# mega_shield_0_1.net
KiCad netlist of a schematic drawn in EAGLE
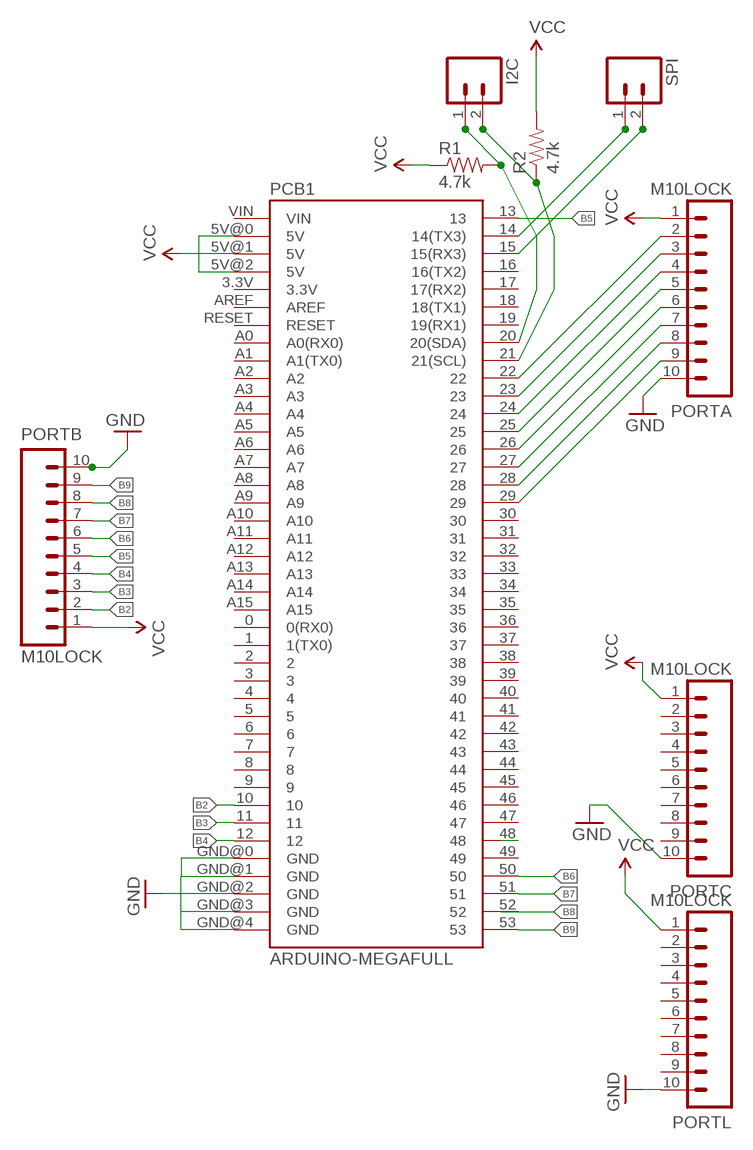
[diagram p0: schematic, sheet 1]

(export (version "E")
  (design (tool "Eeschema 10.0.6"))
  (components
    (comp (ref "I2C")
      (value "M02PTH")
      (footprint "eagle-import:1X02")
      (libsource (lib "eagle-import") (part "M02PTH"))
    )
    (comp (ref "PCB1")
      (value "ARDUINO-MEGAFULL")
      (footprint "eagle-import:ARDUINO_MEGA")
      (libsource (lib "eagle-import") (part "ARDUINO-MEGAFULL"))
    )
    (comp (ref "PORTA")
      (value "M10LOCK")
      (footprint "eagle-import:1X10_LOCK")
      (libsource (lib "eagle-import") (part "M10LOCK"))
    )
    (comp (ref "PORTB")
      (value "M10LOCK")
      (footprint "eagle-import:1X10_LOCK")
      (libsource (lib "eagle-import") (part "M10LOCK"))
    )
    (comp (ref "PORTC")
      (value "M10LOCK")
      (footprint "eagle-import:1X10_LOCK")
      (libsource (lib "eagle-import") (part "M10LOCK"))
    )
    (comp (ref "PORTL")
      (value "M10LOCK")
      (footprint "eagle-import:1X10_LOCK")
      (libsource (lib "eagle-import") (part "M10LOCK"))
    )
    (comp (ref "R1")
      (value "4.7k")
      (footprint "eagle-import:AXIAL-0.3")
      (libsource (lib "eagle-import") (part "RESISTORPTH1"))
    )
    (comp (ref "R2")
      (value "4.7k")
      (footprint "eagle-import:AXIAL-0.3")
      (libsource (lib "eagle-import") (part "RESISTORPTH1"))
    )
    (comp (ref "SPI")
      (value "M02PTH")
      (footprint "eagle-import:1X02")
      (libsource (lib "eagle-import") (part "M02PTH"))
    )
  )
  (nets
    (net (code "1") (name "B2") (class "Default")
      (node (ref "PCB1") (pin "10") (pinfunction "10_10") (pintype "bidirectional"))
      (node (ref "PORTB") (pin "2") (pinfunction "2_2") (pintype "passive"))
    )
    (net (code "2") (name "B3") (class "Default")
      (node (ref "PCB1") (pin "11") (pinfunction "11_11") (pintype "bidirectional"))
      (node (ref "PORTB") (pin "3") (pinfunction "3_3") (pintype "passive"))
    )
    (net (code "3") (name "B4") (class "Default")
      (node (ref "PCB1") (pin "12") (pinfunction "12_12") (pintype "bidirectional"))
      (node (ref "PORTB") (pin "4") (pinfunction "4_4") (pintype "passive"))
    )
    (net (code "4") (name "B5") (class "Default")
      (node (ref "PCB1") (pin "13") (pinfunction "13_13") (pintype "bidirectional"))
      (node (ref "PORTB") (pin "5") (pinfunction "5_5") (pintype "passive"))
    )
    (net (code "5") (name "B6") (class "Default")
      (node (ref "PCB1") (pin "50") (pinfunction "50_50") (pintype "bidirectional"))
      (node (ref "PORTB") (pin "6") (pinfunction "6_6") (pintype "passive"))
    )
    (net (code "6") (name "B7") (class "Default")
      (node (ref "PCB1") (pin "51") (pinfunction "51_51") (pintype "bidirectional"))
      (node (ref "PORTB") (pin "7") (pinfunction "7_7") (pintype "passive"))
    )
    (net (code "7") (name "B8") (class "Default")
      (node (ref "PORTB") (pin "8") (pinfunction "8_8") (pintype "passive"))
    )
    (net (code "8") (name "B9") (class "Default")
      (node (ref "PCB1") (pin "53") (pinfunction "53_53") (pintype "bidirectional"))
      (node (ref "PORTB") (pin "9") (pinfunction "9_9") (pintype "passive"))
    )
    (net (code "9") (name "GND") (class "Default")
      (node (ref "PCB1") (pin "GND@0") (pinfunction "GND_GND@0") (pintype "bidirectional"))
      (node (ref "PCB1") (pin "GND@1") (pinfunction "GND_GND@1") (pintype "bidirectional"))
      (node (ref "PCB1") (pin "GND@2") (pinfunction "GND_GND@2") (pintype "bidirectional"))
      (node (ref "PCB1") (pin "GND@3") (pinfunction "GND_GND@3") (pintype "bidirectional"))
      (node (ref "PCB1") (pin "GND@4") (pinfunction "GND_GND@4") (pintype "bidirectional"))
      (node (ref "PORTA") (pin "10") (pinfunction "10_10") (pintype "passive"))
      (node (ref "PORTB") (pin "10") (pinfunction "10_10") (pintype "passive"))
      (node (ref "PORTC") (pin "10") (pinfunction "10_10") (pintype "passive"))
      (node (ref "PORTL") (pin "10") (pinfunction "10_10") (pintype "passive"))
    )
    (net (code "10") (name "Net-(PCB1-14(TX3))") (class "Default")
      (node (ref "PCB1") (pin "14") (pinfunction "14(TX3)_14") (pintype "bidirectional"))
      (node (ref "SPI") (pin "1") (pinfunction "1_1") (pintype "passive"))
    )
    (net (code "11") (name "Net-(PCB1-15(RX3))") (class "Default")
      (node (ref "PCB1") (pin "15") (pinfunction "15(RX3)_15") (pintype "bidirectional"))
      (node (ref "SPI") (pin "2") (pinfunction "2_2") (pintype "passive"))
    )
    (net (code "12") (name "Net-(PCB1-20(SDA))") (class "Default")
      (node (ref "I2C") (pin "1") (pinfunction "1_1") (pintype "passive"))
      (node (ref "PCB1") (pin "20") (pinfunction "20(SDA)_20") (pintype "bidirectional"))
      (node (ref "R1") (pin "P$2") (pinfunction "2_P$2") (pintype "passive"))
    )
    (net (code "13") (name "Net-(PCB1-21(SCL))") (class "Default")
      (node (ref "I2C") (pin "2") (pinfunction "2_2") (pintype "passive"))
      (node (ref "PCB1") (pin "21") (pinfunction "21(SCL)_21") (pintype "bidirectional"))
      (node (ref "R2") (pin "P$1") (pinfunction "1_P$1") (pintype "passive"))
    )
    (net (code "14") (name "Net-(PCB1-Pad22)") (class "Default")
      (node (ref "PCB1") (pin "22") (pinfunction "22_22") (pintype "bidirectional"))
      (node (ref "PORTA") (pin "2") (pinfunction "2_2") (pintype "passive"))
    )
    (net (code "15") (name "Net-(PCB1-Pad23)") (class "Default")
      (node (ref "PCB1") (pin "23") (pinfunction "23_23") (pintype "bidirectional"))
      (node (ref "PORTA") (pin "3") (pinfunction "3_3") (pintype "passive"))
    )
    (net (code "16") (name "Net-(PCB1-Pad24)") (class "Default")
      (node (ref "PCB1") (pin "24") (pinfunction "24_24") (pintype "bidirectional"))
      (node (ref "PORTA") (pin "4") (pinfunction "4_4") (pintype "passive"))
    )
    (net (code "17") (name "Net-(PCB1-Pad25)") (class "Default")
      (node (ref "PCB1") (pin "25") (pinfunction "25_25") (pintype "bidirectional"))
      (node (ref "PORTA") (pin "5") (pinfunction "5_5") (pintype "passive"))
    )
    (net (code "18") (name "Net-(PCB1-Pad26)") (class "Default")
      (node (ref "PCB1") (pin "26") (pinfunction "26_26") (pintype "bidirectional"))
      (node (ref "PORTA") (pin "6") (pinfunction "6_6") (pintype "passive"))
    )
    (net (code "19") (name "Net-(PCB1-Pad27)") (class "Default")
      (node (ref "PCB1") (pin "27") (pinfunction "27_27") (pintype "bidirectional"))
      (node (ref "PORTA") (pin "7") (pinfunction "7_7") (pintype "passive"))
    )
    (net (code "20") (name "Net-(PCB1-Pad28)") (class "Default")
      (node (ref "PCB1") (pin "28") (pinfunction "28_28") (pintype "bidirectional"))
      (node (ref "PORTA") (pin "8") (pinfunction "8_8") (pintype "passive"))
    )
    (net (code "21") (name "Net-(PCB1-Pad29)") (class "Default")
      (node (ref "PCB1") (pin "29") (pinfunction "29_29") (pintype "bidirectional"))
      (node (ref "PORTA") (pin "9") (pinfunction "9_9") (pintype "passive"))
    )
    (net (code "22") (name "VCC") (class "Default")
      (node (ref "PCB1") (pin "5V@0") (pinfunction "5V_5V@0") (pintype "bidirectional"))
      (node (ref "PCB1") (pin "5V@1") (pinfunction "5V_5V@1") (pintype "bidirectional"))
      (node (ref "PCB1") (pin "5V@2") (pinfunction "5V_5V@2") (pintype "bidirectional"))
      (node (ref "PORTA") (pin "1") (pinfunction "1_1") (pintype "passive"))
      (node (ref "PORTB") (pin "1") (pinfunction "1_1") (pintype "passive"))
      (node (ref "PORTC") (pin "1") (pinfunction "1_1") (pintype "passive"))
      (node (ref "PORTL") (pin "1") (pinfunction "1_1") (pintype "passive"))
      (node (ref "R1") (pin "P$1") (pinfunction "1_P$1") (pintype "passive"))
      (node (ref "R2") (pin "P$2") (pinfunction "2_P$2") (pintype "passive"))
    )
    (net (code "23") (name "unconnected-(PCB1-0(RX0)-Pad0)") (class "Default")
      (node (ref "PCB1") (pin "0") (pinfunction "0(RX0)_0") (pintype "bidirectional"))
    )
    (net (code "24") (name "unconnected-(PCB1-1(TX0)-Pad1)") (class "Default")
      (node (ref "PCB1") (pin "1") (pinfunction "1(TX0)_1") (pintype "bidirectional"))
    )
    (net (code "25") (name "unconnected-(PCB1-16(TX2)-Pad16)") (class "Default")
      (node (ref "PCB1") (pin "16") (pinfunction "16(TX2)_16") (pintype "bidirectional"))
    )
    (net (code "26") (name "unconnected-(PCB1-17(RX2)-Pad17)") (class "Default")
      (node (ref "PCB1") (pin "17") (pinfunction "17(RX2)_17") (pintype "bidirectional"))
    )
    (net (code "27") (name "unconnected-(PCB1-18(TX1)-Pad18)") (class "Default")
      (node (ref "PCB1") (pin "18") (pinfunction "18(TX1)_18") (pintype "bidirectional"))
    )
    (net (code "28") (name "unconnected-(PCB1-19(RX1)-Pad19)") (class "Default")
      (node (ref "PCB1") (pin "19") (pinfunction "19(RX1)_19") (pintype "bidirectional"))
    )
    (net (code "29") (name "unconnected-(PCB1-A0(RX0)-PadA0)") (class "Default")
      (node (ref "PCB1") (pin "A0") (pinfunction "A0(RX0)_A0") (pintype "bidirectional"))
    )
    (net (code "30") (name "unconnected-(PCB1-A1(TX0)-PadA1)") (class "Default")
      (node (ref "PCB1") (pin "A1") (pinfunction "A1(TX0)_A1") (pintype "bidirectional"))
    )
    (net (code "31") (name "unconnected-(PCB1-Pad2)") (class "Default")
      (node (ref "PCB1") (pin "2") (pinfunction "2_2") (pintype "bidirectional"))
    )
    (net (code "32") (name "unconnected-(PCB1-Pad3)") (class "Default")
      (node (ref "PCB1") (pin "3") (pinfunction "3_3") (pintype "bidirectional"))
    )
    (net (code "33") (name "unconnected-(PCB1-Pad3.3V)") (class "Default")
      (node (ref "PCB1") (pin "3.3V") (pinfunction "3.3V_3.3V") (pintype "bidirectional"))
    )
    (net (code "34") (name "unconnected-(PCB1-Pad4)") (class "Default")
      (node (ref "PCB1") (pin "4") (pinfunction "4_4") (pintype "bidirectional"))
    )
    (net (code "35") (name "unconnected-(PCB1-Pad5)") (class "Default")
      (node (ref "PCB1") (pin "5") (pinfunction "5_5") (pintype "bidirectional"))
    )
    (net (code "36") (name "unconnected-(PCB1-Pad6)") (class "Default")
      (node (ref "PCB1") (pin "6") (pinfunction "6_6") (pintype "bidirectional"))
    )
    (net (code "37") (name "unconnected-(PCB1-Pad7)") (class "Default")
      (node (ref "PCB1") (pin "7") (pinfunction "7_7") (pintype "bidirectional"))
    )
    (net (code "38") (name "unconnected-(PCB1-Pad8)") (class "Default")
      (node (ref "PCB1") (pin "8") (pinfunction "8_8") (pintype "bidirectional"))
    )
    (net (code "39") (name "unconnected-(PCB1-Pad9)") (class "Default")
      (node (ref "PCB1") (pin "9") (pinfunction "9_9") (pintype "bidirectional"))
    )
    (net (code "40") (name "unconnected-(PCB1-Pad30)") (class "Default")
      (node (ref "PCB1") (pin "30") (pinfunction "30_30") (pintype "bidirectional"))
    )
    (net (code "41") (name "unconnected-(PCB1-Pad31)") (class "Default")
      (node (ref "PCB1") (pin "31") (pinfunction "31_31") (pintype "bidirectional"))
    )
    (net (code "42") (name "unconnected-(PCB1-Pad32)") (class "Default")
      (node (ref "PCB1") (pin "32") (pinfunction "32_32") (pintype "bidirectional"))
    )
    (net (code "43") (name "unconnected-(PCB1-Pad33)") (class "Default")
      (node (ref "PCB1") (pin "33") (pinfunction "33_33") (pintype "bidirectional"))
    )
    (net (code "44") (name "unconnected-(PCB1-Pad34)") (class "Default")
      (node (ref "PCB1") (pin "34") (pinfunction "34_34") (pintype "bidirectional"))
    )
    (net (code "45") (name "unconnected-(PCB1-Pad35)") (class "Default")
      (node (ref "PCB1") (pin "35") (pinfunction "35_35") (pintype "bidirectional"))
    )
    (net (code "46") (name "unconnected-(PCB1-Pad36)") (class "Default")
      (node (ref "PCB1") (pin "36") (pinfunction "36_36") (pintype "bidirectional"))
    )
    (net (code "47") (name "unconnected-(PCB1-Pad37)") (class "Default")
      (node (ref "PCB1") (pin "37") (pinfunction "37_37") (pintype "bidirectional"))
    )
    (net (code "48") (name "unconnected-(PCB1-Pad38)") (class "Default")
      (node (ref "PCB1") (pin "38") (pinfunction "38_38") (pintype "bidirectional"))
    )
    (net (code "49") (name "unconnected-(PCB1-Pad39)") (class "Default")
      (node (ref "PCB1") (pin "39") (pinfunction "39_39") (pintype "bidirectional"))
    )
    (net (code "50") (name "unconnected-(PCB1-Pad40)") (class "Default")
      (node (ref "PCB1") (pin "40") (pinfunction "40_40") (pintype "bidirectional"))
    )
    (net (code "51") (name "unconnected-(PCB1-Pad41)") (class "Default")
      (node (ref "PCB1") (pin "41") (pinfunction "41_41") (pintype "bidirectional"))
    )
    (net (code "52") (name "unconnected-(PCB1-Pad42)") (class "Default")
      (node (ref "PCB1") (pin "42") (pinfunction "42_42") (pintype "bidirectional"))
    )
    (net (code "53") (name "unconnected-(PCB1-Pad43)") (class "Default")
      (node (ref "PCB1") (pin "43") (pinfunction "43_43") (pintype "bidirectional"))
    )
    (net (code "54") (name "unconnected-(PCB1-Pad44)") (class "Default")
      (node (ref "PCB1") (pin "44") (pinfunction "44_44") (pintype "bidirectional"))
    )
    (net (code "55") (name "unconnected-(PCB1-Pad45)") (class "Default")
      (node (ref "PCB1") (pin "45") (pinfunction "45_45") (pintype "bidirectional"))
    )
    (net (code "56") (name "unconnected-(PCB1-Pad46)") (class "Default")
      (node (ref "PCB1") (pin "46") (pinfunction "46_46") (pintype "bidirectional"))
    )
    (net (code "57") (name "unconnected-(PCB1-Pad47)") (class "Default")
      (node (ref "PCB1") (pin "47") (pinfunction "47_47") (pintype "bidirectional"))
    )
    (net (code "58") (name "unconnected-(PCB1-Pad48)") (class "Default")
      (node (ref "PCB1") (pin "48") (pinfunction "48_48") (pintype "bidirectional"))
    )
    (net (code "59") (name "unconnected-(PCB1-Pad49)") (class "Default")
      (node (ref "PCB1") (pin "49") (pinfunction "49_49") (pintype "bidirectional"))
    )
    (net (code "60") (name "unconnected-(PCB1-Pad52)") (class "Default")
      (node (ref "PCB1") (pin "52") (pinfunction "52_52") (pintype "bidirectional"))
    )
    (net (code "61") (name "unconnected-(PCB1-PadA2)") (class "Default")
      (node (ref "PCB1") (pin "A2") (pinfunction "A2_A2") (pintype "bidirectional"))
    )
    (net (code "62") (name "unconnected-(PCB1-PadA3)") (class "Default")
      (node (ref "PCB1") (pin "A3") (pinfunction "A3_A3") (pintype "bidirectional"))
    )
    (net (code "63") (name "unconnected-(PCB1-PadA4)") (class "Default")
      (node (ref "PCB1") (pin "A4") (pinfunction "A4_A4") (pintype "bidirectional"))
    )
    (net (code "64") (name "unconnected-(PCB1-PadA5)") (class "Default")
      (node (ref "PCB1") (pin "A5") (pinfunction "A5_A5") (pintype "bidirectional"))
    )
    (net (code "65") (name "unconnected-(PCB1-PadA6)") (class "Default")
      (node (ref "PCB1") (pin "A6") (pinfunction "A6_A6") (pintype "bidirectional"))
    )
    (net (code "66") (name "unconnected-(PCB1-PadA7)") (class "Default")
      (node (ref "PCB1") (pin "A7") (pinfunction "A7_A7") (pintype "bidirectional"))
    )
    (net (code "67") (name "unconnected-(PCB1-PadA8)") (class "Default")
      (node (ref "PCB1") (pin "A8") (pinfunction "A8_A8") (pintype "bidirectional"))
    )
    (net (code "68") (name "unconnected-(PCB1-PadA9)") (class "Default")
      (node (ref "PCB1") (pin "A9") (pinfunction "A9_A9") (pintype "bidirectional"))
    )
    (net (code "69") (name "unconnected-(PCB1-PadA10)") (class "Default")
      (node (ref "PCB1") (pin "A10") (pinfunction "A10_A10") (pintype "bidirectional"))
    )
    (net (code "70") (name "unconnected-(PCB1-PadA11)") (class "Default")
      (node (ref "PCB1") (pin "A11") (pinfunction "A11_A11") (pintype "bidirectional"))
    )
    (net (code "71") (name "unconnected-(PCB1-PadA12)") (class "Default")
      (node (ref "PCB1") (pin "A12") (pinfunction "A12_A12") (pintype "bidirectional"))
    )
    (net (code "72") (name "unconnected-(PCB1-PadA13)") (class "Default")
      (node (ref "PCB1") (pin "A13") (pinfunction "A13_A13") (pintype "bidirectional"))
    )
    (net (code "73") (name "unconnected-(PCB1-PadA14)") (class "Default")
      (node (ref "PCB1") (pin "A14") (pinfunction "A14_A14") (pintype "bidirectional"))
    )
    (net (code "74") (name "unconnected-(PCB1-PadA15)") (class "Default")
      (node (ref "PCB1") (pin "A15") (pinfunction "A15_A15") (pintype "bidirectional"))
    )
    (net (code "75") (name "unconnected-(PCB1-PadAREF)") (class "Default")
      (node (ref "PCB1") (pin "AREF") (pinfunction "AREF_AREF") (pintype "bidirectional"))
    )
    (net (code "76") (name "unconnected-(PCB1-PadRESET)") (class "Default")
      (node (ref "PCB1") (pin "RESET") (pinfunction "RESET_RESET") (pintype "bidirectional"))
    )
    (net (code "77") (name "unconnected-(PCB1-PadVIN)") (class "Default")
      (node (ref "PCB1") (pin "VIN") (pinfunction "VIN_VIN") (pintype "bidirectional"))
    )
    (net (code "78") (name "unconnected-(PORTC-Pad2)") (class "Default")
      (node (ref "PORTC") (pin "2") (pinfunction "2_2") (pintype "passive"))
    )
    (net (code "79") (name "unconnected-(PORTC-Pad3)") (class "Default")
      (node (ref "PORTC") (pin "3") (pinfunction "3_3") (pintype "passive"))
    )
    (net (code "80") (name "unconnected-(PORTC-Pad4)") (class "Default")
      (node (ref "PORTC") (pin "4") (pinfunction "4_4") (pintype "passive"))
    )
    (net (code "81") (name "unconnected-(PORTC-Pad5)") (class "Default")
      (node (ref "PORTC") (pin "5") (pinfunction "5_5") (pintype "passive"))
    )
    (net (code "82") (name "unconnected-(PORTC-Pad6)") (class "Default")
      (node (ref "PORTC") (pin "6") (pinfunction "6_6") (pintype "passive"))
    )
    (net (code "83") (name "unconnected-(PORTC-Pad7)") (class "Default")
      (node (ref "PORTC") (pin "7") (pinfunction "7_7") (pintype "passive"))
    )
    (net (code "84") (name "unconnected-(PORTC-Pad8)") (class "Default")
      (node (ref "PORTC") (pin "8") (pinfunction "8_8") (pintype "passive"))
    )
    (net (code "85") (name "unconnected-(PORTC-Pad9)") (class "Default")
      (node (ref "PORTC") (pin "9") (pinfunction "9_9") (pintype "passive"))
    )
    (net (code "86") (name "unconnected-(PORTL-Pad2)") (class "Default")
      (node (ref "PORTL") (pin "2") (pinfunction "2_2") (pintype "passive"))
    )
    (net (code "87") (name "unconnected-(PORTL-Pad3)") (class "Default")
      (node (ref "PORTL") (pin "3") (pinfunction "3_3") (pintype "passive"))
    )
    (net (code "88") (name "unconnected-(PORTL-Pad4)") (class "Default")
      (node (ref "PORTL") (pin "4") (pinfunction "4_4") (pintype "passive"))
    )
    (net (code "89") (name "unconnected-(PORTL-Pad5)") (class "Default")
      (node (ref "PORTL") (pin "5") (pinfunction "5_5") (pintype "passive"))
    )
    (net (code "90") (name "unconnected-(PORTL-Pad6)") (class "Default")
      (node (ref "PORTL") (pin "6") (pinfunction "6_6") (pintype "passive"))
    )
    (net (code "91") (name "unconnected-(PORTL-Pad7)") (class "Default")
      (node (ref "PORTL") (pin "7") (pinfunction "7_7") (pintype "passive"))
    )
    (net (code "92") (name "unconnected-(PORTL-Pad8)") (class "Default")
      (node (ref "PORTL") (pin "8") (pinfunction "8_8") (pintype "passive"))
    )
    (net (code "93") (name "unconnected-(PORTL-Pad9)") (class "Default")
      (node (ref "PORTL") (pin "9") (pinfunction "9_9") (pintype "passive"))
    )
  )
)
